# Motor1.net
KiCad netlist of a schematic drawn in Altium Designer
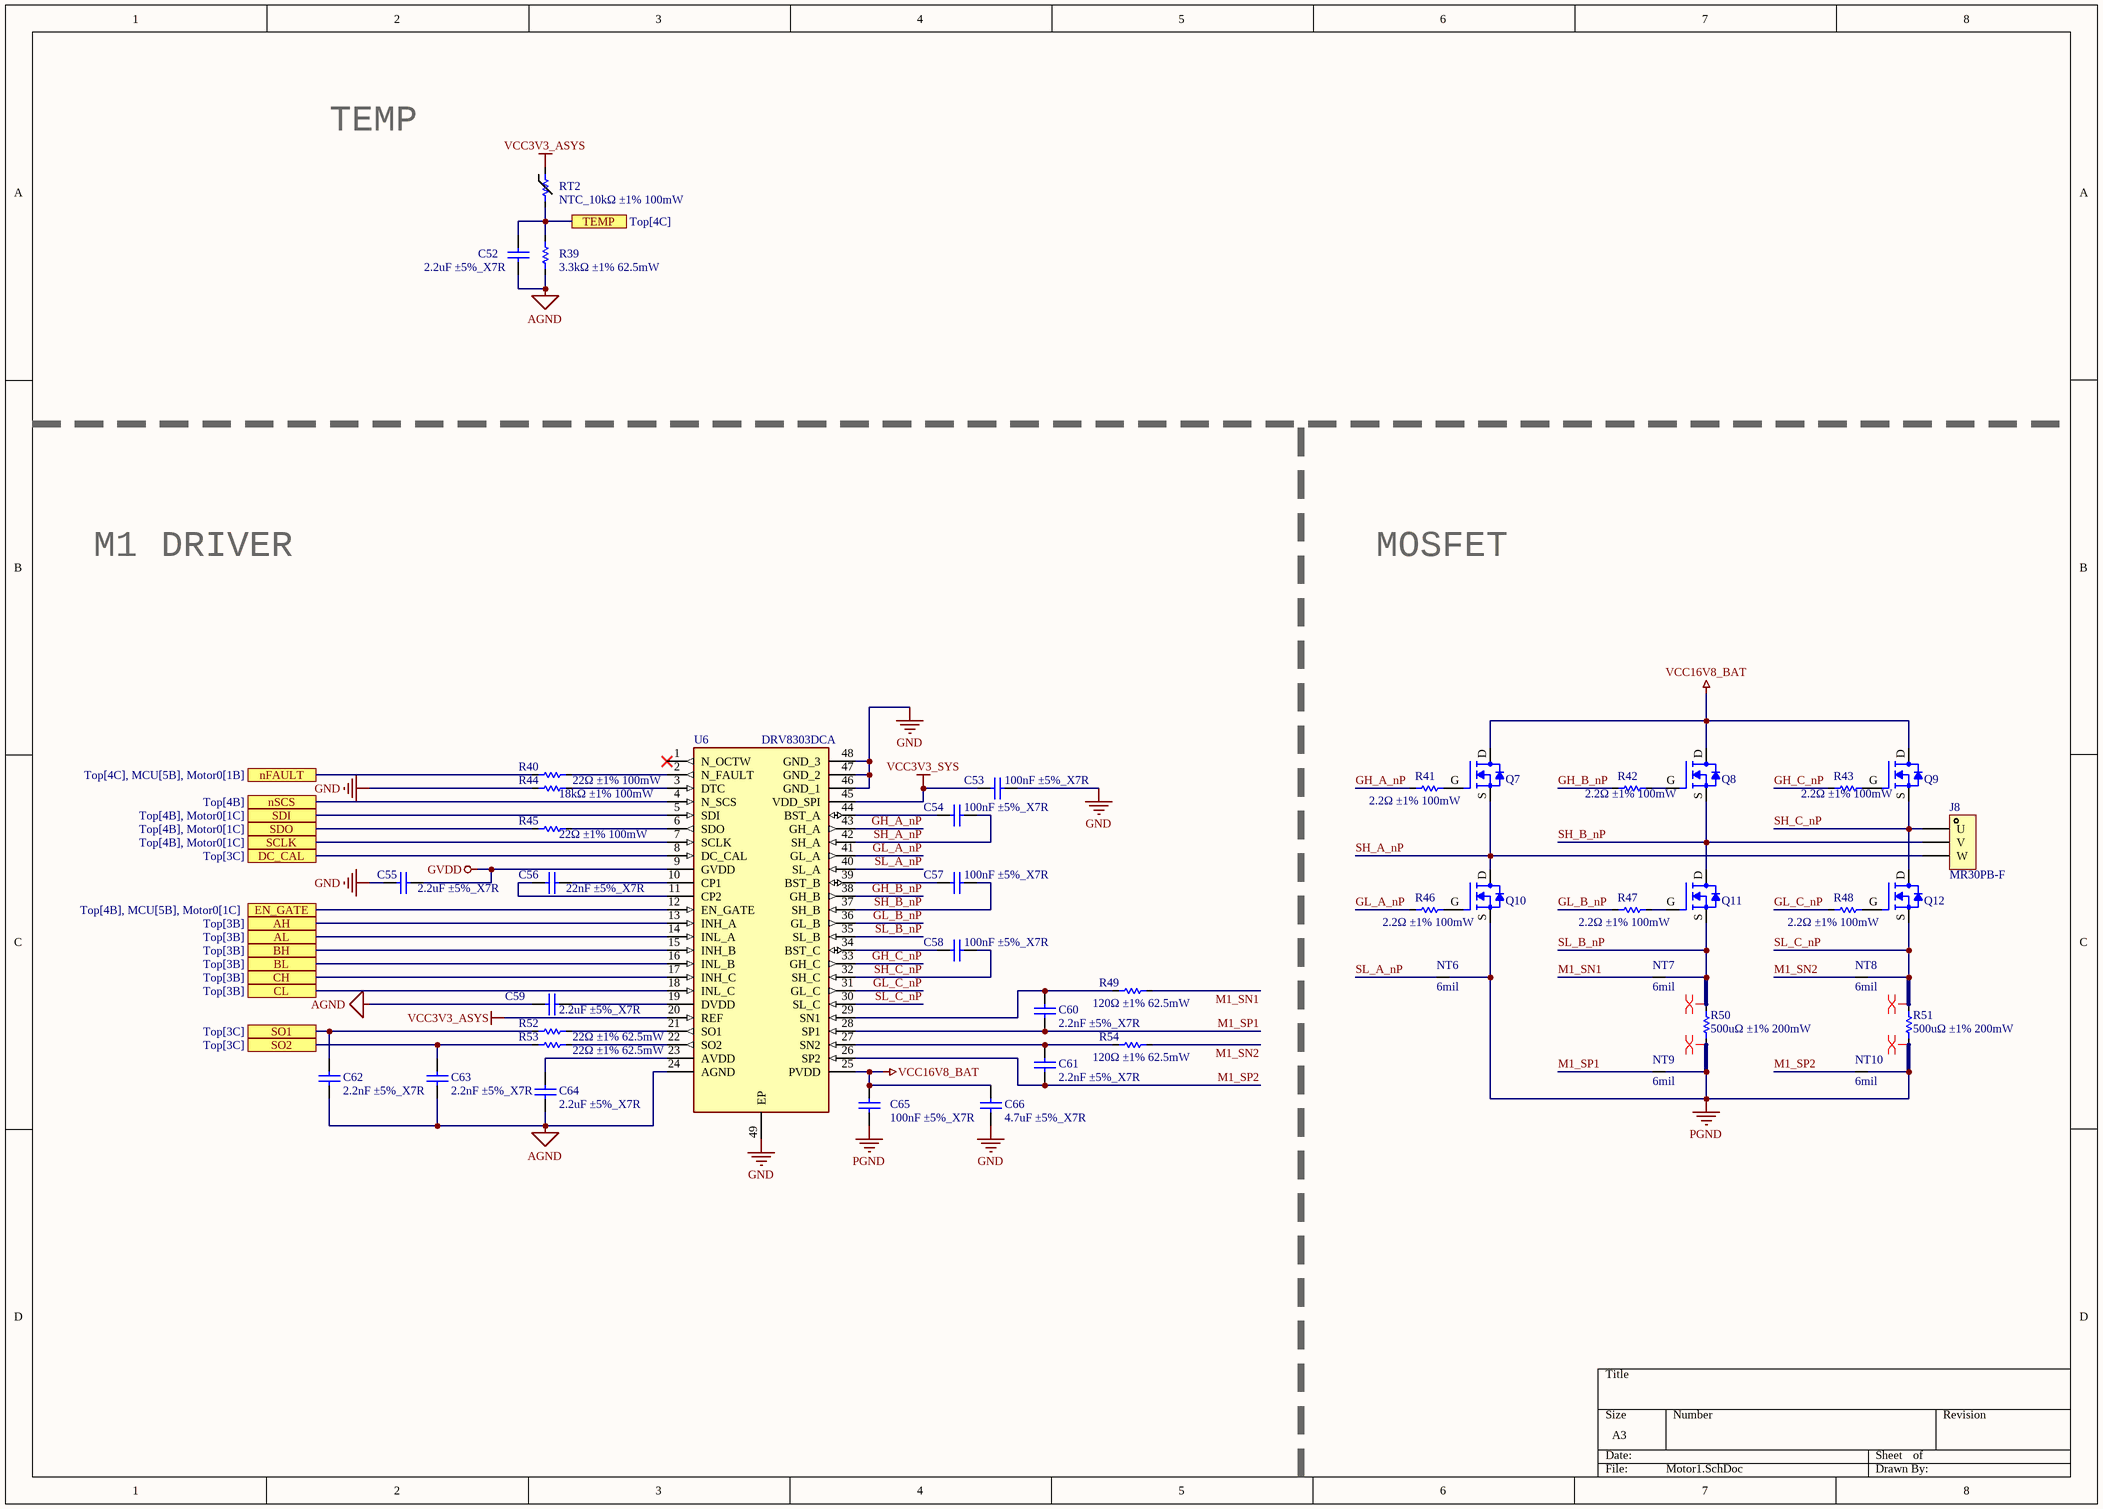
[diagram p0: Motor1.SchDoc]

(export (version "E")
  (design (tool "Eeschema 10.0.6"))
  (components
    (comp (ref "C52")
      (value "2.2uF ±5%_X7R")
      (footprint "WCAP-CSGP_0402_L1W0.5H0.5")
      (description "Capacitor")
      (fields (field (name "PUBLISHER") "Altium Limited"))
      (libsource (lib "Component") (part "Cap"))
    )
    (comp (ref "C53")
      (value "100nF ±5%_X7R")
      (footprint "WCAP-CSGP_0402_L1W0.5H0.5")
      (description "Capacitor")
      (fields (field (name "PUBLISHER") "Altium Limited"))
      (libsource (lib "Component") (part "Cap"))
    )
    (comp (ref "C54")
      (value "100nF ±5%_X7R")
      (footprint "WCAP-CSGP_0402_L1W0.5H0.5")
      (description "Capacitor")
      (fields (field (name "PUBLISHER") "Altium Limited"))
      (libsource (lib "Component") (part "Cap"))
    )
    (comp (ref "C55")
      (value "2.2uF ±5%_X7R")
      (footprint "WCAP-CSGP_0402_L1W0.5H0.5")
      (description "CL05A225KO5NQNC")
      (fields (field (name "PUBLISHER") "Altium Limited"))
      (libsource (lib "Component") (part "Cap"))
    )
    (comp (ref "C56")
      (value "22nF ±5%_X7R")
      (footprint "WCAP-CSGP_0402_L1W0.5H0.5")
      (description "Capacitor")
      (fields (field (name "PUBLISHER") "Altium Limited"))
      (libsource (lib "Component") (part "Cap"))
    )
    (comp (ref "C57")
      (value "100nF ±5%_X7R")
      (footprint "WCAP-CSGP_0402_L1W0.5H0.5")
      (description "Capacitor")
      (fields (field (name "PUBLISHER") "Altium Limited"))
      (libsource (lib "Component") (part "Cap"))
    )
    (comp (ref "C58")
      (value "100nF ±5%_X7R")
      (footprint "WCAP-CSGP_0402_L1W0.5H0.5")
      (description "Capacitor")
      (fields (field (name "PUBLISHER") "Altium Limited"))
      (libsource (lib "Component") (part "Cap"))
    )
    (comp (ref "C59")
      (value "2.2uF ±5%_X7R")
      (footprint "WCAP-CSGP_0402_L1W0.5H0.5")
      (description "CL05A225KO5NQNC")
      (fields (field (name "PUBLISHER") "Altium Limited"))
      (libsource (lib "Component") (part "Cap"))
    )
    (comp (ref "C60")
      (value "2.2nF ±5%_X7R")
      (footprint "WCAP-CSGP_0402_L1W0.5H0.5")
      (description "Capacitor")
      (fields (field (name "PUBLISHER") "Altium Limited"))
      (libsource (lib "Component") (part "Cap"))
    )
    (comp (ref "C61")
      (value "2.2nF ±5%_X7R")
      (footprint "WCAP-CSGP_0402_L1W0.5H0.5")
      (description "Capacitor")
      (fields (field (name "PUBLISHER") "Altium Limited"))
      (libsource (lib "Component") (part "Cap"))
    )
    (comp (ref "C62")
      (value "2.2nF ±5%_X7R")
      (footprint "WCAP-CSGP_0402_L1W0.5H0.5")
      (description "Capacitor")
      (fields (field (name "PUBLISHER") "Altium Limited"))
      (libsource (lib "Component") (part "Cap"))
    )
    (comp (ref "C63")
      (value "2.2nF ±5%_X7R")
      (footprint "WCAP-CSGP_0402_L1W0.5H0.5")
      (description "Capacitor")
      (fields (field (name "PUBLISHER") "Altium Limited"))
      (libsource (lib "Component") (part "Cap"))
    )
    (comp (ref "C64")
      (value "2.2uF ±5%_X7R")
      (footprint "WCAP-CSGP_0402_L1W0.5H0.5")
      (description "CL05A225KO5NQNC")
      (fields (field (name "PUBLISHER") "Altium Limited"))
      (libsource (lib "Component") (part "Cap"))
    )
    (comp (ref "C65")
      (value "100nF ±5%_X7R")
      (footprint "WCAP-CSGP_0402_L1W0.5H0.5")
      (description "Capacitor")
      (fields (field (name "PUBLISHER") "Altium Limited"))
      (libsource (lib "Component") (part "Cap"))
    )
    (comp (ref "C66")
      (value "4.7uF ±5%_X7R")
      (footprint "WCAP-CSGP_0603_L1.6W0.8H0.8_Reflow")
      (description "Capacitor")
      (fields (field (name "PUBLISHER") "Altium Limited"))
      (libsource (lib "Component") (part "Cap"))
    )
    (comp (ref "J8")
      (value "MR30PB-F")
      (footprint "MR30PB-F [Straight] [SMT]")
      (description "驱动器端")
      (libsource (lib "Connectivity_Plugs") (part "MR30PB-F [Straight] [SMT]"))
    )
    (comp (ref "NT6") (value "6mil") (footprint "NETTIE_6mil") (libsource (lib "Component") (part "NETTIE")))
    (comp (ref "NT7") (value "6mil") (footprint "NETTIE_6mil") (libsource (lib "Component") (part "NETTIE")))
    (comp (ref "NT8") (value "6mil") (footprint "NETTIE_6mil") (libsource (lib "Component") (part "NETTIE")))
    (comp (ref "NT9") (value "6mil") (footprint "NETTIE_6mil") (libsource (lib "Component") (part "NETTIE")))
    (comp (ref "NT10") (value "6mil") (footprint "NETTIE_6mil") (libsource (lib "Component") (part "NETTIE")))
    (comp (ref "Q7")
      (value "BSC027N04LSG")
      (footprint "NRVTS10100EMFST1G")
      (description "MOSFET – Power, Single,\r\nN-Channel, PG-TDSON-8\r\nSuperSO8 5x6\r\n40 V, 139 A")
      (fields
        (field (name "MANUFACTURER") "ON Semiconductor")
        (field (name "MANUFACTURER PART NUMBER") "NTMFS4935NT1G")
      )
      (libsource (lib "Component") (part "MOSFET-N"))
    )
    (comp (ref "Q8")
      (value "BSC027N04LSG")
      (footprint "NRVTS10100EMFST1G")
      (description "MOSFET – Power, Single,\r\nN-Channel, PG-TDSON-8\r\nSuperSO8 5x6\r\n40 V, 139 A")
      (fields
        (field (name "MANUFACTURER") "ON Semiconductor")
        (field (name "MANUFACTURER PART NUMBER") "NTMFS4935NT1G")
      )
      (libsource (lib "Component") (part "MOSFET-N"))
    )
    (comp (ref "Q9")
      (value "BSC027N04LSG")
      (footprint "NRVTS10100EMFST1G")
      (description "MOSFET – Power, Single,\r\nN-Channel, PG-TDSON-8\r\nSuperSO8 5x6\r\n40 V, 139 A")
      (fields
        (field (name "MANUFACTURER") "ON Semiconductor")
        (field (name "MANUFACTURER PART NUMBER") "NTMFS4935NT1G")
      )
      (libsource (lib "Component") (part "MOSFET-N"))
    )
    (comp (ref "Q10")
      (value "BSC027N04LSG")
      (footprint "NRVTS10100EMFST1G")
      (description "MOSFET – Power, Single,\r\nN-Channel, PG-TDSON-8\r\nSuperSO8 5x6\r\n40 V, 139 A")
      (fields
        (field (name "MANUFACTURER") "ON Semiconductor")
        (field (name "MANUFACTURER PART NUMBER") "NTMFS4935NT1G")
      )
      (libsource (lib "Component") (part "MOSFET-N"))
    )
    (comp (ref "Q11")
      (value "BSC027N04LSG")
      (footprint "NRVTS10100EMFST1G")
      (description "MOSFET – Power, Single,\r\nN-Channel, PG-TDSON-8\r\nSuperSO8 5x6\r\n40 V, 139 A")
      (fields
        (field (name "MANUFACTURER") "ON Semiconductor")
        (field (name "MANUFACTURER PART NUMBER") "NTMFS4935NT1G")
      )
      (libsource (lib "Component") (part "MOSFET-N"))
    )
    (comp (ref "Q12")
      (value "BSC027N04LSG")
      (footprint "NRVTS10100EMFST1G")
      (description "MOSFET – Power, Single,\r\nN-Channel, PG-TDSON-8\r\nSuperSO8 5x6\r\n40 V, 139 A")
      (fields
        (field (name "MANUFACTURER") "ON Semiconductor")
        (field (name "MANUFACTURER PART NUMBER") "NTMFS4935NT1G")
      )
      (libsource (lib "Component") (part "MOSFET-N"))
    )
    (comp (ref "R39")
      (value "3.3kΩ ±1% 62.5mW")
      (footprint "WRIS-KSKE_0402")
      (description "Resistor")
      (fields (field (name "PUBLISHER") "Altium Limited"))
      (libsource (lib "Component") (part "Res"))
    )
    (comp (ref "R40")
      (value "22Ω ±1% 100mW")
      (footprint "WRIS-KSKE_0402")
      (description "Resistor")
      (fields (field (name "PUBLISHER") "Altium Limited"))
      (libsource (lib "Component") (part "Res"))
    )
    (comp (ref "R41")
      (value "2.2Ω ±1% 100mW")
      (footprint "WRIS-KSKE_0402")
      (description "Resistor")
      (fields (field (name "PUBLISHER") "Altium Limited"))
      (libsource (lib "Component") (part "Res"))
    )
    (comp (ref "R42")
      (value "2.2Ω ±1% 100mW")
      (footprint "WRIS-KSKE_0402")
      (description "Resistor")
      (fields (field (name "PUBLISHER") "Altium Limited"))
      (libsource (lib "Component") (part "Res"))
    )
    (comp (ref "R43")
      (value "2.2Ω ±1% 100mW")
      (footprint "WRIS-KSKE_0402")
      (description "Resistor")
      (fields (field (name "PUBLISHER") "Altium Limited"))
      (libsource (lib "Component") (part "Res"))
    )
    (comp (ref "R44")
      (value "18kΩ ±1% 100mW")
      (footprint "WRIS-KSKE_0402")
      (description "Resistor")
      (fields (field (name "PUBLISHER") "Altium Limited"))
      (libsource (lib "Component") (part "Res"))
    )
    (comp (ref "R45")
      (value "22Ω ±1% 100mW")
      (footprint "WRIS-KSKE_0402")
      (description "Resistor")
      (fields (field (name "PUBLISHER") "Altium Limited"))
      (libsource (lib "Component") (part "Res"))
    )
    (comp (ref "R46")
      (value "2.2Ω ±1% 100mW")
      (footprint "WRIS-KSKE_0402")
      (description "Resistor")
      (fields (field (name "PUBLISHER") "Altium Limited"))
      (libsource (lib "Component") (part "Res"))
    )
    (comp (ref "R47")
      (value "2.2Ω ±1% 100mW")
      (footprint "WRIS-KSKE_0402")
      (description "Resistor")
      (fields (field (name "PUBLISHER") "Altium Limited"))
      (libsource (lib "Component") (part "Res"))
    )
    (comp (ref "R48")
      (value "2.2Ω ±1% 100mW")
      (footprint "WRIS-KSKE_0402")
      (description "Resistor")
      (fields (field (name "PUBLISHER") "Altium Limited"))
      (libsource (lib "Component") (part "Res"))
    )
    (comp (ref "R49")
      (value "120Ω ±1% 62.5mW")
      (footprint "WRIS-KSKE_0402")
      (description "Resistor")
      (fields (field (name "PUBLISHER") "Altium Limited"))
      (libsource (lib "Component") (part "Res"))
    )
    (comp (ref "R50")
      (value "500uΩ ±1% 200mW")
      (footprint "WRIS-KSKE_2512")
      (description "Resistor")
      (fields (field (name "PUBLISHER") "Altium Limited"))
      (libsource (lib "Component") (part "Res"))
    )
    (comp (ref "R51")
      (value "500uΩ ±1% 200mW")
      (footprint "WRIS-KSKE_2512")
      (description "Resistor")
      (fields (field (name "PUBLISHER") "Altium Limited"))
      (libsource (lib "Component") (part "Res"))
    )
    (comp (ref "R52")
      (value "22Ω ±1% 62.5mW")
      (footprint "WRIS-KSKE_0402")
      (description "Resistor")
      (fields (field (name "PUBLISHER") "Altium Limited"))
      (libsource (lib "Component") (part "Res"))
    )
    (comp (ref "R53")
      (value "22Ω ±1% 62.5mW")
      (footprint "WRIS-KSKE_0402")
      (description "Resistor")
      (fields (field (name "PUBLISHER") "Altium Limited"))
      (libsource (lib "Component") (part "Res"))
    )
    (comp (ref "R54")
      (value "120Ω ±1% 62.5mW")
      (footprint "WRIS-KSKE_0402")
      (description "Resistor")
      (fields (field (name "PUBLISHER") "Altium Limited"))
      (libsource (lib "Component") (part "Res"))
    )
    (comp (ref "RT2")
      (value "NTC_10kΩ ±1% 100mW")
      (footprint "WRIS-KSKE_0402")
      (description "THERMISTOR 10K OHM NTC 0402 SMD")
      (libsource (lib "Component") (part "TEMP RES"))
    )
    (comp (ref "U6")
      (value "DRV8303DCA")
      (footprint "SamacSys:SOP50P810X120-49N")
      (description "Integrated Circuit")
      (fields (field (name "MOUSER PART NUMBER") "595-DRV8303DCA"))
      (libsource (lib "*") (part "DRV8303DCA"))
    )
  )
  (nets
    (net (code "1") (name "/AH") (class "Default")
      (node (ref "U6") (pin "13") (pinfunction "INH_A_13") (pintype "input"))
    )
    (net (code "2") (name "/AL") (class "Default")
      (node (ref "U6") (pin "14") (pinfunction "INL_A_14") (pintype "input"))
    )
    (net (code "3") (name "/BH") (class "Default")
      (node (ref "U6") (pin "15") (pinfunction "INH_B_15") (pintype "input"))
    )
    (net (code "4") (name "/BL") (class "Default")
      (node (ref "U6") (pin "16") (pinfunction "INL_B_16") (pintype "input"))
    )
    (net (code "5") (name "/CH") (class "Default")
      (node (ref "U6") (pin "17") (pinfunction "INH_C_17") (pintype "input"))
    )
    (net (code "6") (name "/CL") (class "Default")
      (node (ref "U6") (pin "18") (pinfunction "INL_C_18") (pintype "input"))
    )
    (net (code "7") (name "/DC_CAL") (class "Default")
      (node (ref "U6") (pin "8") (pinfunction "DC_CAL_8") (pintype "input"))
    )
    (net (code "8") (name "/EN_GATE") (class "Default")
      (node (ref "U6") (pin "12") (pinfunction "EN_GATE_12") (pintype "input"))
    )
    (net (code "9") (name "/GH_A_nP") (class "Default")
      (node (ref "R41") (pin "2") (pinfunction "2_2") (pintype "passive"))
      (node (ref "U6") (pin "43") (pinfunction "GH_A_43") (pintype "output"))
    )
    (net (code "10") (name "/GH_B_nP") (class "Default")
      (node (ref "R42") (pin "2") (pinfunction "2_2") (pintype "passive"))
      (node (ref "U6") (pin "38") (pinfunction "GH_B_38") (pintype "output"))
    )
    (net (code "11") (name "/GH_C_nP") (class "Default")
      (node (ref "R43") (pin "2") (pinfunction "2_2") (pintype "passive"))
      (node (ref "U6") (pin "33") (pinfunction "GH_C_33") (pintype "output"))
    )
    (net (code "12") (name "/GL_A_nP") (class "Default")
      (node (ref "R46") (pin "2") (pinfunction "2_2") (pintype "passive"))
      (node (ref "U6") (pin "41") (pinfunction "GL_A_41") (pintype "output"))
    )
    (net (code "13") (name "/GL_B_nP") (class "Default")
      (node (ref "R47") (pin "2") (pinfunction "2_2") (pintype "passive"))
      (node (ref "U6") (pin "36") (pinfunction "GL_B_36") (pintype "output"))
    )
    (net (code "14") (name "/GL_C_nP") (class "Default")
      (node (ref "R48") (pin "2") (pinfunction "2_2") (pintype "passive"))
      (node (ref "U6") (pin "31") (pinfunction "GL_C_31") (pintype "output"))
    )
    (net (code "15") (name "/M1_SN1") (class "Default")
      (node (ref "NT7") (pin "1") (pinfunction "1_1") (pintype "passive"))
      (node (ref "R49") (pin "1") (pinfunction "1_1") (pintype "passive"))
    )
    (net (code "16") (name "/M1_SN2") (class "Default")
      (node (ref "NT8") (pin "1") (pinfunction "1_1") (pintype "passive"))
      (node (ref "R54") (pin "1") (pinfunction "1_1") (pintype "passive"))
    )
    (net (code "17") (name "/M1_SP1") (class "Default")
      (node (ref "C60") (pin "1") (pinfunction "1_1") (pintype "passive"))
      (node (ref "NT9") (pin "1") (pinfunction "1_1") (pintype "passive"))
      (node (ref "U6") (pin "28") (pinfunction "SP1_28") (pintype "input"))
    )
    (net (code "18") (name "/M1_SP2") (class "Default")
      (node (ref "C61") (pin "1") (pinfunction "1_1") (pintype "passive"))
      (node (ref "NT10") (pin "1") (pinfunction "1_1") (pintype "passive"))
      (node (ref "U6") (pin "26") (pinfunction "SP2_26") (pintype "input"))
    )
    (net (code "19") (name "/SCLK") (class "Default")
      (node (ref "U6") (pin "7") (pinfunction "SCLK_7") (pintype "input"))
    )
    (net (code "20") (name "/SDI") (class "Default")
      (node (ref "U6") (pin "5") (pinfunction "SDI_5") (pintype "input"))
    )
    (net (code "21") (name "/SDO") (class "Default")
      (node (ref "R45") (pin "1") (pinfunction "1_1") (pintype "passive"))
    )
    (net (code "22") (name "/SH_A_nP") (class "Default")
      (node (ref "C54") (pin "1") (pinfunction "1_1") (pintype "passive"))
      (node (ref "J8") (pin "3") (pinfunction "W_3") (pintype "passive"))
      (node (ref "Q10") (pin "D") (pinfunction "D_D") (pintype "passive"))
      (node (ref "Q7") (pin "S") (pinfunction "S_S") (pintype "passive"))
      (node (ref "U6") (pin "42") (pinfunction "SH_A_42") (pintype "input"))
    )
    (net (code "23") (name "/SH_B_nP") (class "Default")
      (node (ref "C57") (pin "1") (pinfunction "1_1") (pintype "passive"))
      (node (ref "J8") (pin "2") (pinfunction "V_2") (pintype "passive"))
      (node (ref "Q11") (pin "D") (pinfunction "D_D") (pintype "passive"))
      (node (ref "Q8") (pin "S") (pinfunction "S_S") (pintype "passive"))
      (node (ref "U6") (pin "37") (pinfunction "SH_B_37") (pintype "input"))
    )
    (net (code "24") (name "/SH_C_nP") (class "Default")
      (node (ref "C58") (pin "1") (pinfunction "1_1") (pintype "passive"))
      (node (ref "J8") (pin "1") (pinfunction "U_1") (pintype "passive"))
      (node (ref "Q12") (pin "D") (pinfunction "D_D") (pintype "passive"))
      (node (ref "Q9") (pin "S") (pinfunction "S_S") (pintype "passive"))
      (node (ref "U6") (pin "32") (pinfunction "SH_C_32") (pintype "input"))
    )
    (net (code "25") (name "/SL_A_nP") (class "Default")
      (node (ref "NT6") (pin "2") (pinfunction "2_2") (pintype "passive"))
      (node (ref "U6") (pin "40") (pinfunction "SL_A_40") (pintype "input"))
    )
    (net (code "26") (name "/SL_B_nP") (class "Default")
      (node (ref "NT7") (pin "2") (pinfunction "2_2") (pintype "passive"))
      (node (ref "Q11") (pin "S") (pinfunction "S_S") (pintype "passive"))
      (node (ref "R50") (pin "2") (pinfunction "2_2") (pintype "passive"))
      (node (ref "U6") (pin "35") (pinfunction "SL_B_35") (pintype "input"))
    )
    (net (code "27") (name "/SL_C_nP") (class "Default")
      (node (ref "NT8") (pin "2") (pinfunction "2_2") (pintype "passive"))
      (node (ref "Q12") (pin "S") (pinfunction "S_S") (pintype "passive"))
      (node (ref "R51") (pin "2") (pinfunction "2_2") (pintype "passive"))
      (node (ref "U6") (pin "30") (pinfunction "SL_C_30") (pintype "input"))
    )
    (net (code "28") (name "/SO1") (class "Default")
      (node (ref "C62") (pin "2") (pinfunction "2_2") (pintype "passive"))
      (node (ref "R52") (pin "2") (pinfunction "2_2") (pintype "passive"))
    )
    (net (code "29") (name "/SO2") (class "Default")
      (node (ref "C63") (pin "2") (pinfunction "2_2") (pintype "passive"))
      (node (ref "R53") (pin "2") (pinfunction "2_2") (pintype "passive"))
    )
    (net (code "30") (name "/TEMP") (class "Default")
      (node (ref "C52") (pin "2") (pinfunction "2_2") (pintype "passive"))
      (node (ref "R39") (pin "2") (pinfunction "2_2") (pintype "passive"))
      (node (ref "RT2") (pin "2") (pinfunction "2_2") (pintype "passive"))
    )
    (net (code "31") (name "/nFAULT") (class "Default")
      (node (ref "R40") (pin "1") (pinfunction "1_1") (pintype "passive"))
    )
    (net (code "32") (name "/nSCS") (class "Default")
      (node (ref "U6") (pin "4") (pinfunction "N_SCS_4") (pintype "input"))
    )
    (net (code "33") (name "AGND") (class "Default")
      (node (ref "C52") (pin "1") (pinfunction "1_1") (pintype "passive"))
      (node (ref "C59") (pin "2") (pinfunction "2_2") (pintype "passive"))
      (node (ref "C62") (pin "1") (pinfunction "1_1") (pintype "passive"))
      (node (ref "C63") (pin "1") (pinfunction "1_1") (pintype "passive"))
      (node (ref "C64") (pin "1") (pinfunction "1_1") (pintype "passive"))
      (node (ref "R39") (pin "1") (pinfunction "1_1") (pintype "passive"))
      (node (ref "U6") (pin "24") (pinfunction "AGND_24") (pintype "power_in"))
    )
    (net (code "34") (name "GND") (class "Default")
      (node (ref "C53") (pin "1") (pinfunction "1_1") (pintype "passive"))
      (node (ref "C55") (pin "1") (pinfunction "1_1") (pintype "passive"))
      (node (ref "C66") (pin "1") (pinfunction "1_1") (pintype "passive"))
      (node (ref "R44") (pin "2") (pinfunction "2_2") (pintype "passive"))
      (node (ref "U6") (pin "46") (pinfunction "GND_1_46") (pintype "power_in"))
      (node (ref "U6") (pin "47") (pinfunction "GND_2_47") (pintype "power_in"))
      (node (ref "U6") (pin "48") (pinfunction "GND_3_48") (pintype "power_in"))
      (node (ref "U6") (pin "49") (pinfunction "EP_49") (pintype "passive"))
    )
    (net (code "35") (name "GVDD") (class "Default")
      (node (ref "C55") (pin "2") (pinfunction "2_2") (pintype "passive"))
      (node (ref "U6") (pin "9") (pinfunction "GVDD_9") (pintype "power_in"))
    )
    (net (code "36") (name "Net-(Q7-PadG)") (class "Default")
      (node (ref "Q7") (pin "G") (pinfunction "G_G") (pintype "passive"))
      (node (ref "R41") (pin "1") (pinfunction "1_1") (pintype "passive"))
    )
    (net (code "37") (name "Net-(Q8-PadG)") (class "Default")
      (node (ref "Q8") (pin "G") (pinfunction "G_G") (pintype "passive"))
      (node (ref "R42") (pin "1") (pinfunction "1_1") (pintype "passive"))
    )
    (net (code "38") (name "Net-(Q9-PadG)") (class "Default")
      (node (ref "Q9") (pin "G") (pinfunction "G_G") (pintype "passive"))
      (node (ref "R43") (pin "1") (pinfunction "1_1") (pintype "passive"))
    )
    (net (code "39") (name "Net-(Q10-PadG)") (class "Default")
      (node (ref "Q10") (pin "G") (pinfunction "G_G") (pintype "passive"))
      (node (ref "R46") (pin "1") (pinfunction "1_1") (pintype "passive"))
    )
    (net (code "40") (name "Net-(Q11-PadG)") (class "Default")
      (node (ref "Q11") (pin "G") (pinfunction "G_G") (pintype "passive"))
      (node (ref "R47") (pin "1") (pinfunction "1_1") (pintype "passive"))
    )
    (net (code "41") (name "Net-(Q12-PadG)") (class "Default")
      (node (ref "Q12") (pin "G") (pinfunction "G_G") (pintype "passive"))
      (node (ref "R48") (pin "1") (pinfunction "1_1") (pintype "passive"))
    )
    (net (code "42") (name "Net-(U6-AVDD)") (class "Default")
      (node (ref "C64") (pin "2") (pinfunction "2_2") (pintype "passive"))
      (node (ref "U6") (pin "23") (pinfunction "AVDD_23") (pintype "power_in"))
    )
    (net (code "43") (name "Net-(U6-BST_A)") (class "Default")
      (node (ref "C54") (pin "2") (pinfunction "2_2") (pintype "passive"))
      (node (ref "U6") (pin "44") (pinfunction "BST_A_44") (pintype "bidirectional"))
    )
    (net (code "44") (name "Net-(U6-BST_B)") (class "Default")
      (node (ref "C57") (pin "2") (pinfunction "2_2") (pintype "passive"))
      (node (ref "U6") (pin "39") (pinfunction "BST_B_39") (pintype "bidirectional"))
    )
    (net (code "45") (name "Net-(U6-BST_C)") (class "Default")
      (node (ref "C58") (pin "2") (pinfunction "2_2") (pintype "passive"))
      (node (ref "U6") (pin "34") (pinfunction "BST_C_34") (pintype "bidirectional"))
    )
    (net (code "46") (name "Net-(U6-CP1)") (class "Default")
      (node (ref "C56") (pin "1") (pinfunction "1_1") (pintype "passive"))
      (node (ref "U6") (pin "10") (pinfunction "CP1_10") (pintype "power_in"))
    )
    (net (code "47") (name "Net-(U6-CP2)") (class "Default")
      (node (ref "C56") (pin "2") (pinfunction "2_2") (pintype "passive"))
      (node (ref "U6") (pin "11") (pinfunction "CP2_11") (pintype "power_in"))
    )
    (net (code "48") (name "Net-(U6-DTC)") (class "Default")
      (node (ref "R44") (pin "1") (pinfunction "1_1") (pintype "passive"))
      (node (ref "U6") (pin "3") (pinfunction "DTC_3") (pintype "input"))
    )
    (net (code "49") (name "Net-(U6-DVDD)") (class "Default")
      (node (ref "C59") (pin "1") (pinfunction "1_1") (pintype "passive"))
      (node (ref "U6") (pin "19") (pinfunction "DVDD_19") (pintype "power_in"))
    )
    (net (code "50") (name "Net-(U6-N_FAULT)") (class "Default")
      (node (ref "R40") (pin "2") (pinfunction "2_2") (pintype "passive"))
      (node (ref "U6") (pin "2") (pinfunction "N_FAULT_2") (pintype "output"))
    )
    (net (code "51") (name "Net-(U6-SDO)") (class "Default")
      (node (ref "R45") (pin "2") (pinfunction "2_2") (pintype "passive"))
      (node (ref "U6") (pin "6") (pinfunction "SDO_6") (pintype "output"))
    )
    (net (code "52") (name "Net-(U6-SN1)") (class "Default")
      (node (ref "C60") (pin "2") (pinfunction "2_2") (pintype "passive"))
      (node (ref "R49") (pin "2") (pinfunction "2_2") (pintype "passive"))
      (node (ref "U6") (pin "29") (pinfunction "SN1_29") (pintype "input"))
    )
    (net (code "53") (name "Net-(U6-SN2)") (class "Default")
      (node (ref "C61") (pin "2") (pinfunction "2_2") (pintype "passive"))
      (node (ref "R54") (pin "2") (pinfunction "2_2") (pintype "passive"))
      (node (ref "U6") (pin "27") (pinfunction "SN2_27") (pintype "input"))
    )
    (net (code "54") (name "Net-(U6-SO1)") (class "Default")
      (node (ref "R52") (pin "1") (pinfunction "1_1") (pintype "passive"))
      (node (ref "U6") (pin "21") (pinfunction "SO1_21") (pintype "output"))
    )
    (net (code "55") (name "Net-(U6-SO2)") (class "Default")
      (node (ref "R53") (pin "1") (pinfunction "1_1") (pintype "passive"))
      (node (ref "U6") (pin "22") (pinfunction "SO2_22") (pintype "output"))
    )
    (net (code "56") (name "PGND") (class "Default")
      (node (ref "C65") (pin "1") (pinfunction "1_1") (pintype "passive"))
      (node (ref "NT10") (pin "2") (pinfunction "2_2") (pintype "passive"))
      (node (ref "NT6") (pin "1") (pinfunction "1_1") (pintype "passive"))
      (node (ref "NT9") (pin "2") (pinfunction "2_2") (pintype "passive"))
      (node (ref "Q10") (pin "S") (pinfunction "S_S") (pintype "passive"))
      (node (ref "R50") (pin "1") (pinfunction "1_1") (pintype "passive"))
      (node (ref "R51") (pin "1") (pinfunction "1_1") (pintype "passive"))
    )
    (net (code "57") (name "VCC3V3_ASYS") (class "Default")
      (node (ref "RT2") (pin "1") (pinfunction "1_1") (pintype "passive"))
      (node (ref "U6") (pin "20") (pinfunction "REF_20") (pintype "input"))
    )
    (net (code "58") (name "VCC3V3_SYS") (class "Default")
      (node (ref "C53") (pin "2") (pinfunction "2_2") (pintype "passive"))
      (node (ref "U6") (pin "45") (pinfunction "VDD_SPI_45") (pintype "power_in"))
    )
    (net (code "59") (name "VCC16V8_BAT") (class "Default")
      (node (ref "C65") (pin "2") (pinfunction "2_2") (pintype "passive"))
      (node (ref "C66") (pin "2") (pinfunction "2_2") (pintype "passive"))
      (node (ref "Q7") (pin "D") (pinfunction "D_D") (pintype "passive"))
      (node (ref "Q8") (pin "D") (pinfunction "D_D") (pintype "passive"))
      (node (ref "Q9") (pin "D") (pinfunction "D_D") (pintype "passive"))
      (node (ref "U6") (pin "25") (pinfunction "PVDD_25") (pintype "power_in"))
    )
    (net (code "60") (name "unconnected-(U6-N_OCTW-Pad1)") (class "Default")
      (node (ref "U6") (pin "1") (pinfunction "N_OCTW_1") (pintype "output+no_connect"))
    )
  )
)
